# Sheet1.net
KiCad netlist of a schematic drawn in Altium Designer
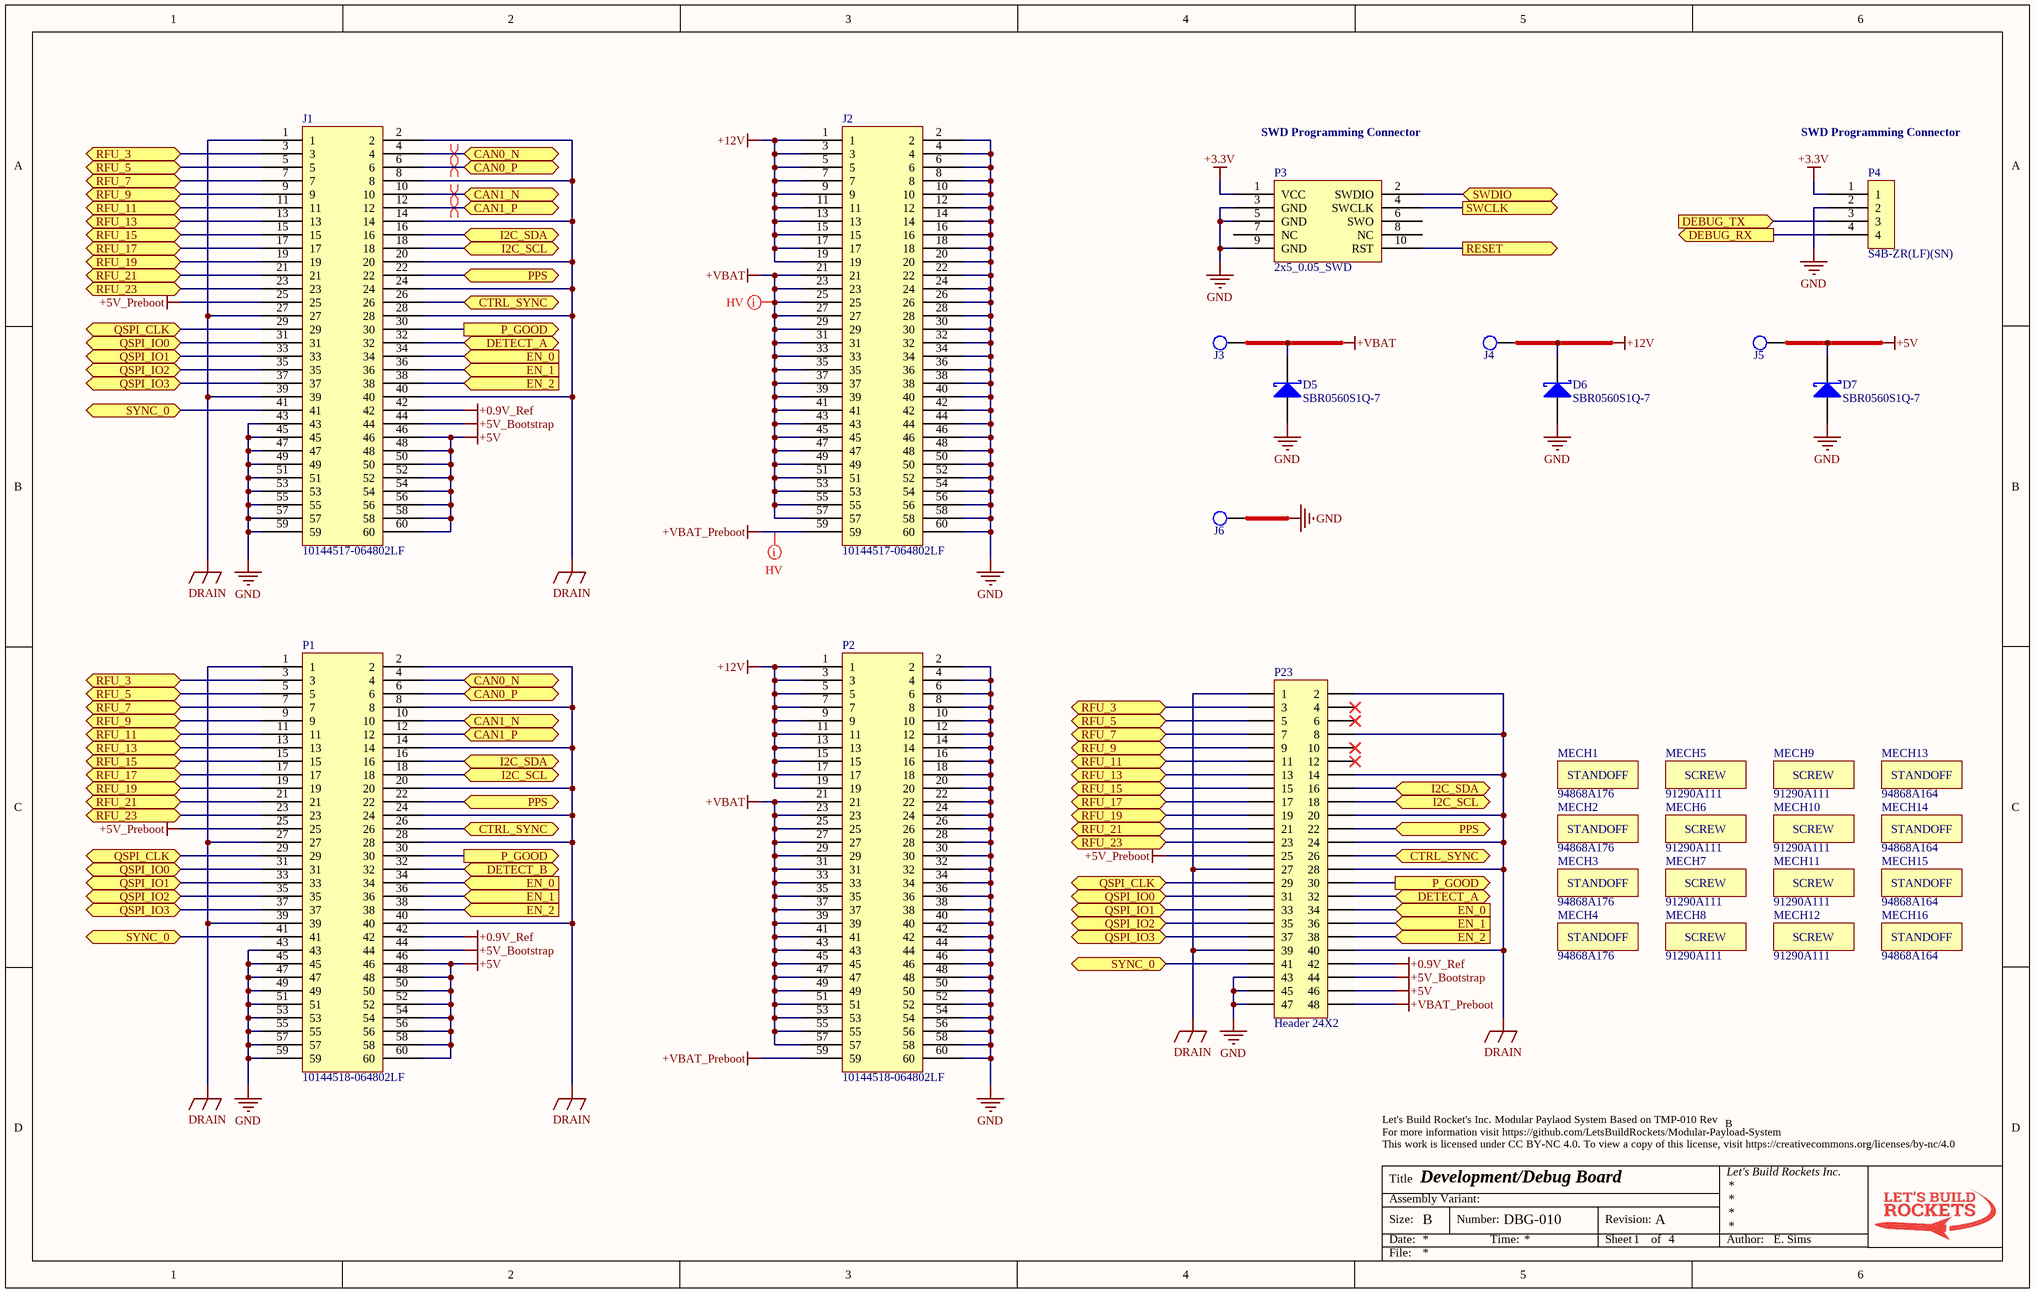
[diagram p0: Sheet1.SchDoc]

(export (version "E")
  (design (tool "Eeschema 10.0.6"))
  (components
    (comp (ref "D5")
      (value "SBR0560S1Q-7")
      (footprint "SOD123")
      (libsource (lib "ModularPayload") (part "SBR0560S1Q-7"))
    )
    (comp (ref "D6")
      (value "SBR0560S1Q-7")
      (footprint "SOD123")
      (libsource (lib "ModularPayload") (part "SBR0560S1Q-7"))
    )
    (comp (ref "D7")
      (value "SBR0560S1Q-7")
      (footprint "SOD123")
      (libsource (lib "ModularPayload") (part "SBR0560S1Q-7"))
    )
    (comp (ref "J1")
      (value "10144517-064802LF")
      (footprint "10144517-064802LF")
      (libsource (lib "ModularPayload") (part "10144517-064802LF"))
    )
    (comp (ref "J2")
      (value "10144517-064802LF")
      (footprint "10144517-064802LF")
      (libsource (lib "ModularPayload") (part "10144517-064802LF"))
    )
    (comp (ref "J3") (value "Banana") (footprint "CT3151SP-2") (libsource (lib "TP") (part "CT3151SP-2")))
    (comp (ref "J4") (value "Banana") (footprint "CT3151SP-2") (libsource (lib "TP") (part "CT3151SP-2")))
    (comp (ref "J5") (value "Banana") (footprint "CT3151SP-2") (libsource (lib "TP") (part "CT3151SP-2")))
    (comp (ref "J6") (value "Banana") (footprint "CT3151SP-0") (libsource (lib "TP") (part "CT3151SP-0")))
    (comp (ref "MECH1")
      (value "94868A176")
      (footprint "94868A176")
      (libsource (lib "ModularPayload") (part "94868A176"))
    )
    (comp (ref "MECH2")
      (value "94868A176")
      (footprint "94868A176")
      (libsource (lib "ModularPayload") (part "94868A176"))
    )
    (comp (ref "MECH3")
      (value "94868A176")
      (footprint "94868A176")
      (libsource (lib "ModularPayload") (part "94868A176"))
    )
    (comp (ref "MECH4")
      (value "94868A176")
      (footprint "94868A176")
      (libsource (lib "ModularPayload") (part "94868A176"))
    )
    (comp (ref "MECH5")
      (value "91290A111")
      (footprint "91290A111")
      (libsource (lib "ModularPayload") (part "91290A111"))
    )
    (comp (ref "MECH6")
      (value "91290A111")
      (footprint "91290A111")
      (libsource (lib "ModularPayload") (part "91290A111"))
    )
    (comp (ref "MECH7")
      (value "91290A111")
      (footprint "91290A111")
      (libsource (lib "ModularPayload") (part "91290A111"))
    )
    (comp (ref "MECH8")
      (value "91290A111")
      (footprint "91290A111")
      (libsource (lib "ModularPayload") (part "91290A111"))
    )
    (comp (ref "MECH9")
      (value "91290A111")
      (footprint "91290A111")
      (libsource (lib "ModularPayload") (part "91290A111"))
    )
    (comp (ref "MECH10")
      (value "91290A111")
      (footprint "91290A111")
      (libsource (lib "ModularPayload") (part "91290A111"))
    )
    (comp (ref "MECH11")
      (value "91290A111")
      (footprint "91290A111")
      (libsource (lib "ModularPayload") (part "91290A111"))
    )
    (comp (ref "MECH12")
      (value "91290A111")
      (footprint "91290A111")
      (libsource (lib "ModularPayload") (part "91290A111"))
    )
    (comp (ref "MECH13")
      (value "94868A164")
      (footprint "94868A164")
      (libsource (lib "ModularPayload") (part "94868A164"))
    )
    (comp (ref "MECH14")
      (value "94868A164")
      (footprint "94868A164")
      (libsource (lib "ModularPayload") (part "94868A164"))
    )
    (comp (ref "MECH15")
      (value "94868A164")
      (footprint "94868A164")
      (libsource (lib "ModularPayload") (part "94868A164"))
    )
    (comp (ref "MECH16")
      (value "94868A164")
      (footprint "94868A164")
      (libsource (lib "ModularPayload") (part "94868A164"))
    )
    (comp (ref "P1")
      (value "10144518-064802LF")
      (footprint "10144518-064802LF")
      (libsource (lib "ModularPayload") (part "10144518-064802LF"))
    )
    (comp (ref "P2")
      (value "10144518-064802LF")
      (footprint "10144518-064802LF")
      (libsource (lib "ModularPayload") (part "10144518-064802LF"))
    )
    (comp (ref "P3")
      (value "2x5_0.05_SWD")
      (footprint "2x5_0.05_R")
      (libsource (lib "ModularPayload") (part "2x5_0.05_SWD"))
    )
    (comp (ref "P4")
      (value "S4B-ZR(LF)(SN)")
      (footprint "S4B-ZR(LF)(SN)")
      (libsource (lib "ModularPayload") (part "S4B-ZR(LF)(SN)"))
    )
    (comp (ref "P23")
      (value "Header 24X2")
      (footprint "HDR2X24")
      (description "Header, 24-Pin, Dual row")
      (fields (field (name "PUBLISHER") "Altium Limited"))
      (libsource (lib "Miscellaneous Connectors") (part "Header 24X2"))
    )
  )
  (nets
    (net (code "1") (name "+0.9V_Ref") (class "Default")
      (node (ref "J1") (pin "42") (pinfunction "42_42") (pintype "passive"))
      (node (ref "P1") (pin "42") (pinfunction "42_42") (pintype "passive"))
      (node (ref "P23") (pin "42") (pinfunction "42_42") (pintype "passive"))
    )
    (net (code "2") (name "+3.3V") (class "Default")
      (node (ref "P3") (pin "1") (pinfunction "VCC_1") (pintype "passive"))
      (node (ref "P4") (pin "1") (pinfunction "1_1") (pintype "passive"))
    )
    (net (code "3") (name "+5V") (class "Default")
      (node (ref "D7") (pin "K") (pinfunction "K_K") (pintype "passive"))
      (node (ref "J1") (pin "46") (pinfunction "46_46") (pintype "passive"))
      (node (ref "J1") (pin "48") (pinfunction "48_48") (pintype "passive"))
      (node (ref "J1") (pin "50") (pinfunction "50_50") (pintype "passive"))
      (node (ref "J1") (pin "52") (pinfunction "52_52") (pintype "passive"))
      (node (ref "J1") (pin "54") (pinfunction "54_54") (pintype "passive"))
      (node (ref "J1") (pin "56") (pinfunction "56_56") (pintype "passive"))
      (node (ref "J1") (pin "58") (pinfunction "58_58") (pintype "passive"))
      (node (ref "J1") (pin "60") (pinfunction "60_60") (pintype "passive"))
      (node (ref "J5") (pin "1") (pintype "passive"))
      (node (ref "P1") (pin "46") (pinfunction "46_46") (pintype "passive"))
      (node (ref "P1") (pin "48") (pinfunction "48_48") (pintype "passive"))
      (node (ref "P1") (pin "50") (pinfunction "50_50") (pintype "passive"))
      (node (ref "P1") (pin "52") (pinfunction "52_52") (pintype "passive"))
      (node (ref "P1") (pin "54") (pinfunction "54_54") (pintype "passive"))
      (node (ref "P1") (pin "56") (pinfunction "56_56") (pintype "passive"))
      (node (ref "P1") (pin "58") (pinfunction "58_58") (pintype "passive"))
      (node (ref "P1") (pin "60") (pinfunction "60_60") (pintype "passive"))
      (node (ref "P23") (pin "46") (pinfunction "46_46") (pintype "passive"))
    )
    (net (code "4") (name "+5V_Bootstrap") (class "Default")
      (node (ref "J1") (pin "44") (pinfunction "44_44") (pintype "passive"))
      (node (ref "P1") (pin "44") (pinfunction "44_44") (pintype "passive"))
      (node (ref "P23") (pin "44") (pinfunction "44_44") (pintype "passive"))
    )
    (net (code "5") (name "+5V_Preboot") (class "Default")
      (node (ref "J1") (pin "25") (pinfunction "25_25") (pintype "passive"))
      (node (ref "P1") (pin "25") (pinfunction "25_25") (pintype "passive"))
      (node (ref "P23") (pin "25") (pinfunction "25_25") (pintype "passive"))
    )
    (net (code "6") (name "+12V") (class "Default")
      (node (ref "D6") (pin "K") (pinfunction "K_K") (pintype "passive"))
      (node (ref "J2") (pin "1") (pinfunction "1_1") (pintype "passive"))
      (node (ref "J2") (pin "11") (pinfunction "11_11") (pintype "passive"))
      (node (ref "J2") (pin "13") (pinfunction "13_13") (pintype "passive"))
      (node (ref "J2") (pin "15") (pinfunction "15_15") (pintype "passive"))
      (node (ref "J2") (pin "17") (pinfunction "17_17") (pintype "passive"))
      (node (ref "J2") (pin "19") (pinfunction "19_19") (pintype "passive"))
      (node (ref "J2") (pin "3") (pinfunction "3_3") (pintype "passive"))
      (node (ref "J2") (pin "5") (pinfunction "5_5") (pintype "passive"))
      (node (ref "J2") (pin "7") (pinfunction "7_7") (pintype "passive"))
      (node (ref "J2") (pin "9") (pinfunction "9_9") (pintype "passive"))
      (node (ref "J4") (pin "1") (pintype "passive"))
      (node (ref "P2") (pin "1") (pinfunction "1_1") (pintype "passive"))
      (node (ref "P2") (pin "11") (pinfunction "11_11") (pintype "passive"))
      (node (ref "P2") (pin "13") (pinfunction "13_13") (pintype "passive"))
      (node (ref "P2") (pin "15") (pinfunction "15_15") (pintype "passive"))
      (node (ref "P2") (pin "17") (pinfunction "17_17") (pintype "passive"))
      (node (ref "P2") (pin "19") (pinfunction "19_19") (pintype "passive"))
      (node (ref "P2") (pin "3") (pinfunction "3_3") (pintype "passive"))
      (node (ref "P2") (pin "5") (pinfunction "5_5") (pintype "passive"))
      (node (ref "P2") (pin "7") (pinfunction "7_7") (pintype "passive"))
      (node (ref "P2") (pin "9") (pinfunction "9_9") (pintype "passive"))
    )
    (net (code "7") (name "+VBAT") (class "Default")
      (node (ref "D5") (pin "K") (pinfunction "K_K") (pintype "passive"))
      (node (ref "J2") (pin "21") (pinfunction "21_21") (pintype "passive"))
      (node (ref "J2") (pin "23") (pinfunction "23_23") (pintype "passive"))
      (node (ref "J2") (pin "25") (pinfunction "25_25") (pintype "passive"))
      (node (ref "J2") (pin "27") (pinfunction "27_27") (pintype "passive"))
      (node (ref "J2") (pin "29") (pinfunction "29_29") (pintype "passive"))
      (node (ref "J2") (pin "31") (pinfunction "31_31") (pintype "passive"))
      (node (ref "J2") (pin "33") (pinfunction "33_33") (pintype "passive"))
      (node (ref "J2") (pin "35") (pinfunction "35_35") (pintype "passive"))
      (node (ref "J2") (pin "37") (pinfunction "37_37") (pintype "passive"))
      (node (ref "J2") (pin "39") (pinfunction "39_39") (pintype "passive"))
      (node (ref "J2") (pin "41") (pinfunction "41_41") (pintype "passive"))
      (node (ref "J2") (pin "43") (pinfunction "43_43") (pintype "passive"))
      (node (ref "J2") (pin "45") (pinfunction "45_45") (pintype "passive"))
      (node (ref "J2") (pin "47") (pinfunction "47_47") (pintype "passive"))
      (node (ref "J2") (pin "49") (pinfunction "49_49") (pintype "passive"))
      (node (ref "J2") (pin "51") (pinfunction "51_51") (pintype "passive"))
      (node (ref "J2") (pin "53") (pinfunction "53_53") (pintype "passive"))
      (node (ref "J2") (pin "55") (pinfunction "55_55") (pintype "passive"))
      (node (ref "J2") (pin "57") (pinfunction "57_57") (pintype "passive"))
      (node (ref "J3") (pin "1") (pintype "passive"))
      (node (ref "P2") (pin "21") (pinfunction "21_21") (pintype "passive"))
      (node (ref "P2") (pin "23") (pinfunction "23_23") (pintype "passive"))
      (node (ref "P2") (pin "25") (pinfunction "25_25") (pintype "passive"))
      (node (ref "P2") (pin "27") (pinfunction "27_27") (pintype "passive"))
      (node (ref "P2") (pin "29") (pinfunction "29_29") (pintype "passive"))
      (node (ref "P2") (pin "31") (pinfunction "31_31") (pintype "passive"))
      (node (ref "P2") (pin "33") (pinfunction "33_33") (pintype "passive"))
      (node (ref "P2") (pin "35") (pinfunction "35_35") (pintype "passive"))
      (node (ref "P2") (pin "37") (pinfunction "37_37") (pintype "passive"))
      (node (ref "P2") (pin "39") (pinfunction "39_39") (pintype "passive"))
      (node (ref "P2") (pin "41") (pinfunction "41_41") (pintype "passive"))
      (node (ref "P2") (pin "43") (pinfunction "43_43") (pintype "passive"))
      (node (ref "P2") (pin "45") (pinfunction "45_45") (pintype "passive"))
      (node (ref "P2") (pin "47") (pinfunction "47_47") (pintype "passive"))
      (node (ref "P2") (pin "49") (pinfunction "49_49") (pintype "passive"))
      (node (ref "P2") (pin "51") (pinfunction "51_51") (pintype "passive"))
      (node (ref "P2") (pin "53") (pinfunction "53_53") (pintype "passive"))
      (node (ref "P2") (pin "55") (pinfunction "55_55") (pintype "passive"))
      (node (ref "P2") (pin "57") (pinfunction "57_57") (pintype "passive"))
    )
    (net (code "8") (name "+VBAT_Preboot") (class "Default")
      (node (ref "J2") (pin "59") (pinfunction "59_59") (pintype "passive"))
      (node (ref "P2") (pin "59") (pinfunction "59_59") (pintype "passive"))
      (node (ref "P23") (pin "48") (pinfunction "48_48") (pintype "passive"))
    )
    (net (code "9") (name "/CAN0_N") (class "Default")
      (node (ref "J1") (pin "4") (pinfunction "4_4") (pintype "passive"))
      (node (ref "P1") (pin "4") (pinfunction "4_4") (pintype "passive"))
    )
    (net (code "10") (name "/CAN0_P") (class "Default")
      (node (ref "J1") (pin "6") (pinfunction "6_6") (pintype "passive"))
      (node (ref "P1") (pin "6") (pinfunction "6_6") (pintype "passive"))
    )
    (net (code "11") (name "/CAN1_N") (class "Default")
      (node (ref "J1") (pin "10") (pinfunction "10_10") (pintype "passive"))
      (node (ref "P1") (pin "10") (pinfunction "10_10") (pintype "passive"))
    )
    (net (code "12") (name "/CAN1_P") (class "Default")
      (node (ref "J1") (pin "12") (pinfunction "12_12") (pintype "passive"))
      (node (ref "P1") (pin "12") (pinfunction "12_12") (pintype "passive"))
    )
    (net (code "13") (name "/CTRL_SYNC") (class "Default")
      (node (ref "J1") (pin "26") (pinfunction "26_26") (pintype "passive"))
      (node (ref "P1") (pin "26") (pinfunction "26_26") (pintype "passive"))
      (node (ref "P23") (pin "26") (pinfunction "26_26") (pintype "passive"))
    )
    (net (code "14") (name "/DEBUG_RX") (class "Default")
      (node (ref "P4") (pin "4") (pinfunction "4_4") (pintype "passive"))
    )
    (net (code "15") (name "/DEBUG_TX") (class "Default")
      (node (ref "P4") (pin "3") (pinfunction "3_3") (pintype "passive"))
    )
    (net (code "16") (name "/DETECT_A") (class "Default")
      (node (ref "J1") (pin "32") (pinfunction "32_32") (pintype "passive"))
      (node (ref "P23") (pin "32") (pinfunction "32_32") (pintype "passive"))
    )
    (net (code "17") (name "/DETECT_B") (class "Default")
      (node (ref "P1") (pin "32") (pinfunction "32_32") (pintype "passive"))
    )
    (net (code "18") (name "/EN_0") (class "Default")
      (node (ref "J1") (pin "34") (pinfunction "34_34") (pintype "passive"))
      (node (ref "P1") (pin "34") (pinfunction "34_34") (pintype "passive"))
      (node (ref "P23") (pin "34") (pinfunction "34_34") (pintype "passive"))
    )
    (net (code "19") (name "/EN_1") (class "Default")
      (node (ref "J1") (pin "36") (pinfunction "36_36") (pintype "passive"))
      (node (ref "P1") (pin "36") (pinfunction "36_36") (pintype "passive"))
      (node (ref "P23") (pin "36") (pinfunction "36_36") (pintype "passive"))
    )
    (net (code "20") (name "/EN_2") (class "Default")
      (node (ref "J1") (pin "38") (pinfunction "38_38") (pintype "passive"))
      (node (ref "P1") (pin "38") (pinfunction "38_38") (pintype "passive"))
      (node (ref "P23") (pin "38") (pinfunction "38_38") (pintype "passive"))
    )
    (net (code "21") (name "/I2C_SCL") (class "Default")
      (node (ref "J1") (pin "18") (pinfunction "18_18") (pintype "passive"))
      (node (ref "P1") (pin "18") (pinfunction "18_18") (pintype "passive"))
      (node (ref "P23") (pin "18") (pinfunction "18_18") (pintype "passive"))
    )
    (net (code "22") (name "/I2C_SDA") (class "Default")
      (node (ref "J1") (pin "16") (pinfunction "16_16") (pintype "passive"))
      (node (ref "P1") (pin "16") (pinfunction "16_16") (pintype "passive"))
      (node (ref "P23") (pin "16") (pinfunction "16_16") (pintype "passive"))
    )
    (net (code "23") (name "/PPS") (class "Default")
      (node (ref "J1") (pin "22") (pinfunction "22_22") (pintype "passive"))
      (node (ref "P1") (pin "22") (pinfunction "22_22") (pintype "passive"))
      (node (ref "P23") (pin "22") (pinfunction "22_22") (pintype "passive"))
    )
    (net (code "24") (name "/P_GOOD") (class "Default")
      (node (ref "J1") (pin "30") (pinfunction "30_30") (pintype "passive"))
      (node (ref "P1") (pin "30") (pinfunction "30_30") (pintype "passive"))
      (node (ref "P23") (pin "30") (pinfunction "30_30") (pintype "passive"))
    )
    (net (code "25") (name "/QSPI_CLK") (class "Default")
      (node (ref "J1") (pin "29") (pinfunction "29_29") (pintype "passive"))
      (node (ref "P1") (pin "29") (pinfunction "29_29") (pintype "passive"))
      (node (ref "P23") (pin "29") (pinfunction "29_29") (pintype "passive"))
    )
    (net (code "26") (name "/QSPI_IO0") (class "Default")
      (node (ref "J1") (pin "31") (pinfunction "31_31") (pintype "passive"))
      (node (ref "P1") (pin "31") (pinfunction "31_31") (pintype "passive"))
      (node (ref "P23") (pin "31") (pinfunction "31_31") (pintype "passive"))
    )
    (net (code "27") (name "/QSPI_IO1") (class "Default")
      (node (ref "J1") (pin "33") (pinfunction "33_33") (pintype "passive"))
      (node (ref "P1") (pin "33") (pinfunction "33_33") (pintype "passive"))
      (node (ref "P23") (pin "33") (pinfunction "33_33") (pintype "passive"))
    )
    (net (code "28") (name "/QSPI_IO2") (class "Default")
      (node (ref "J1") (pin "35") (pinfunction "35_35") (pintype "passive"))
      (node (ref "P1") (pin "35") (pinfunction "35_35") (pintype "passive"))
      (node (ref "P23") (pin "35") (pinfunction "35_35") (pintype "passive"))
    )
    (net (code "29") (name "/QSPI_IO3") (class "Default")
      (node (ref "J1") (pin "37") (pinfunction "37_37") (pintype "passive"))
      (node (ref "P1") (pin "37") (pinfunction "37_37") (pintype "passive"))
      (node (ref "P23") (pin "37") (pinfunction "37_37") (pintype "passive"))
    )
    (net (code "30") (name "/RESET") (class "Default")
      (node (ref "P3") (pin "10") (pinfunction "RST_10") (pintype "passive"))
    )
    (net (code "31") (name "/RFU_3") (class "Default")
      (node (ref "J1") (pin "3") (pinfunction "3_3") (pintype "passive"))
      (node (ref "P1") (pin "3") (pinfunction "3_3") (pintype "passive"))
      (node (ref "P23") (pin "3") (pinfunction "3_3") (pintype "passive"))
    )
    (net (code "32") (name "/RFU_5") (class "Default")
      (node (ref "J1") (pin "5") (pinfunction "5_5") (pintype "passive"))
      (node (ref "P1") (pin "5") (pinfunction "5_5") (pintype "passive"))
      (node (ref "P23") (pin "5") (pinfunction "5_5") (pintype "passive"))
    )
    (net (code "33") (name "/RFU_7") (class "Default")
      (node (ref "J1") (pin "7") (pinfunction "7_7") (pintype "passive"))
      (node (ref "P1") (pin "7") (pinfunction "7_7") (pintype "passive"))
      (node (ref "P23") (pin "7") (pinfunction "7_7") (pintype "passive"))
    )
    (net (code "34") (name "/RFU_9") (class "Default")
      (node (ref "J1") (pin "9") (pinfunction "9_9") (pintype "passive"))
      (node (ref "P1") (pin "9") (pinfunction "9_9") (pintype "passive"))
      (node (ref "P23") (pin "9") (pinfunction "9_9") (pintype "passive"))
    )
    (net (code "35") (name "/RFU_11") (class "Default")
      (node (ref "J1") (pin "11") (pinfunction "11_11") (pintype "passive"))
      (node (ref "P1") (pin "11") (pinfunction "11_11") (pintype "passive"))
      (node (ref "P23") (pin "11") (pinfunction "11_11") (pintype "passive"))
    )
    (net (code "36") (name "/RFU_13") (class "Default")
      (node (ref "J1") (pin "13") (pinfunction "13_13") (pintype "passive"))
      (node (ref "P1") (pin "13") (pinfunction "13_13") (pintype "passive"))
      (node (ref "P23") (pin "13") (pinfunction "13_13") (pintype "passive"))
    )
    (net (code "37") (name "/RFU_15") (class "Default")
      (node (ref "J1") (pin "15") (pinfunction "15_15") (pintype "passive"))
      (node (ref "P1") (pin "15") (pinfunction "15_15") (pintype "passive"))
      (node (ref "P23") (pin "15") (pinfunction "15_15") (pintype "passive"))
    )
    (net (code "38") (name "/RFU_17") (class "Default")
      (node (ref "J1") (pin "17") (pinfunction "17_17") (pintype "passive"))
      (node (ref "P1") (pin "17") (pinfunction "17_17") (pintype "passive"))
      (node (ref "P23") (pin "17") (pinfunction "17_17") (pintype "passive"))
    )
    (net (code "39") (name "/RFU_19") (class "Default")
      (node (ref "J1") (pin "19") (pinfunction "19_19") (pintype "passive"))
      (node (ref "P1") (pin "19") (pinfunction "19_19") (pintype "passive"))
      (node (ref "P23") (pin "19") (pinfunction "19_19") (pintype "passive"))
    )
    (net (code "40") (name "/RFU_21") (class "Default")
      (node (ref "J1") (pin "21") (pinfunction "21_21") (pintype "passive"))
      (node (ref "P1") (pin "21") (pinfunction "21_21") (pintype "passive"))
      (node (ref "P23") (pin "21") (pinfunction "21_21") (pintype "passive"))
    )
    (net (code "41") (name "/RFU_23") (class "Default")
      (node (ref "J1") (pin "23") (pinfunction "23_23") (pintype "passive"))
      (node (ref "P1") (pin "23") (pinfunction "23_23") (pintype "passive"))
      (node (ref "P23") (pin "23") (pinfunction "23_23") (pintype "passive"))
    )
    (net (code "42") (name "/SWCLK") (class "Default")
      (node (ref "P3") (pin "4") (pinfunction "SWCLK_4") (pintype "passive"))
    )
    (net (code "43") (name "/SWDIO") (class "Default")
      (node (ref "P3") (pin "2") (pinfunction "SWDIO_2") (pintype "passive"))
    )
    (net (code "44") (name "/SYNC_0") (class "Default")
      (node (ref "J1") (pin "41") (pinfunction "41_41") (pintype "passive"))
      (node (ref "P1") (pin "41") (pinfunction "41_41") (pintype "passive"))
      (node (ref "P23") (pin "41") (pinfunction "41_41") (pintype "passive"))
    )
    (net (code "45") (name "DRAIN") (class "Default")
      (node (ref "J1") (pin "1") (pinfunction "1_1") (pintype "passive"))
      (node (ref "J1") (pin "14") (pinfunction "14_14") (pintype "passive"))
      (node (ref "J1") (pin "2") (pinfunction "2_2") (pintype "passive"))
      (node (ref "J1") (pin "20") (pinfunction "20_20") (pintype "passive"))
      (node (ref "J1") (pin "24") (pinfunction "24_24") (pintype "passive"))
      (node (ref "J1") (pin "27") (pinfunction "27_27") (pintype "passive"))
      (node (ref "J1") (pin "28") (pinfunction "28_28") (pintype "passive"))
      (node (ref "J1") (pin "39") (pinfunction "39_39") (pintype "passive"))
      (node (ref "J1") (pin "40") (pinfunction "40_40") (pintype "passive"))
      (node (ref "J1") (pin "8") (pinfunction "8_8") (pintype "passive"))
      (node (ref "P1") (pin "1") (pinfunction "1_1") (pintype "passive"))
      (node (ref "P1") (pin "14") (pinfunction "14_14") (pintype "passive"))
      (node (ref "P1") (pin "2") (pinfunction "2_2") (pintype "passive"))
      (node (ref "P1") (pin "20") (pinfunction "20_20") (pintype "passive"))
      (node (ref "P1") (pin "24") (pinfunction "24_24") (pintype "passive"))
      (node (ref "P1") (pin "27") (pinfunction "27_27") (pintype "passive"))
      (node (ref "P1") (pin "28") (pinfunction "28_28") (pintype "passive"))
      (node (ref "P1") (pin "39") (pinfunction "39_39") (pintype "passive"))
      (node (ref "P1") (pin "40") (pinfunction "40_40") (pintype "passive"))
      (node (ref "P1") (pin "8") (pinfunction "8_8") (pintype "passive"))
      (node (ref "P23") (pin "1") (pinfunction "1_1") (pintype "passive"))
      (node (ref "P23") (pin "14") (pinfunction "14_14") (pintype "passive"))
      (node (ref "P23") (pin "2") (pinfunction "2_2") (pintype "passive"))
      (node (ref "P23") (pin "20") (pinfunction "20_20") (pintype "passive"))
      (node (ref "P23") (pin "24") (pinfunction "24_24") (pintype "passive"))
      (node (ref "P23") (pin "27") (pinfunction "27_27") (pintype "passive"))
      (node (ref "P23") (pin "28") (pinfunction "28_28") (pintype "passive"))
      (node (ref "P23") (pin "39") (pinfunction "39_39") (pintype "passive"))
      (node (ref "P23") (pin "40") (pinfunction "40_40") (pintype "passive"))
      (node (ref "P23") (pin "8") (pinfunction "8_8") (pintype "passive"))
    )
    (net (code "46") (name "GND") (class "Default")
      (node (ref "D5") (pin "A") (pinfunction "A_A") (pintype "passive"))
      (node (ref "D6") (pin "A") (pinfunction "A_A") (pintype "passive"))
      (node (ref "D7") (pin "A") (pinfunction "A_A") (pintype "passive"))
      (node (ref "J1") (pin "43") (pinfunction "43_43") (pintype "passive"))
      (node (ref "J1") (pin "45") (pinfunction "45_45") (pintype "passive"))
      (node (ref "J1") (pin "47") (pinfunction "47_47") (pintype "passive"))
      (node (ref "J1") (pin "49") (pinfunction "49_49") (pintype "passive"))
      (node (ref "J1") (pin "51") (pinfunction "51_51") (pintype "passive"))
      (node (ref "J1") (pin "53") (pinfunction "53_53") (pintype "passive"))
      (node (ref "J1") (pin "55") (pinfunction "55_55") (pintype "passive"))
      (node (ref "J1") (pin "57") (pinfunction "57_57") (pintype "passive"))
      (node (ref "J1") (pin "59") (pinfunction "59_59") (pintype "passive"))
      (node (ref "J2") (pin "10") (pinfunction "10_10") (pintype "passive"))
      (node (ref "J2") (pin "12") (pinfunction "12_12") (pintype "passive"))
      (node (ref "J2") (pin "14") (pinfunction "14_14") (pintype "passive"))
      (node (ref "J2") (pin "16") (pinfunction "16_16") (pintype "passive"))
      (node (ref "J2") (pin "18") (pinfunction "18_18") (pintype "passive"))
      (node (ref "J2") (pin "2") (pinfunction "2_2") (pintype "passive"))
      (node (ref "J2") (pin "20") (pinfunction "20_20") (pintype "passive"))
      (node (ref "J2") (pin "22") (pinfunction "22_22") (pintype "passive"))
      (node (ref "J2") (pin "24") (pinfunction "24_24") (pintype "passive"))
      (node (ref "J2") (pin "26") (pinfunction "26_26") (pintype "passive"))
      (node (ref "J2") (pin "28") (pinfunction "28_28") (pintype "passive"))
      (node (ref "J2") (pin "30") (pinfunction "30_30") (pintype "passive"))
      (node (ref "J2") (pin "32") (pinfunction "32_32") (pintype "passive"))
      (node (ref "J2") (pin "34") (pinfunction "34_34") (pintype "passive"))
      (node (ref "J2") (pin "36") (pinfunction "36_36") (pintype "passive"))
      (node (ref "J2") (pin "38") (pinfunction "38_38") (pintype "passive"))
      (node (ref "J2") (pin "4") (pinfunction "4_4") (pintype "passive"))
      (node (ref "J2") (pin "40") (pinfunction "40_40") (pintype "passive"))
      (node (ref "J2") (pin "42") (pinfunction "42_42") (pintype "passive"))
      (node (ref "J2") (pin "44") (pinfunction "44_44") (pintype "passive"))
      (node (ref "J2") (pin "46") (pinfunction "46_46") (pintype "passive"))
      (node (ref "J2") (pin "48") (pinfunction "48_48") (pintype "passive"))
      (node (ref "J2") (pin "50") (pinfunction "50_50") (pintype "passive"))
      (node (ref "J2") (pin "52") (pinfunction "52_52") (pintype "passive"))
      (node (ref "J2") (pin "54") (pinfunction "54_54") (pintype "passive"))
      (node (ref "J2") (pin "56") (pinfunction "56_56") (pintype "passive"))
      (node (ref "J2") (pin "58") (pinfunction "58_58") (pintype "passive"))
      (node (ref "J2") (pin "6") (pinfunction "6_6") (pintype "passive"))
      (node (ref "J2") (pin "60") (pinfunction "60_60") (pintype "passive"))
      (node (ref "J2") (pin "8") (pinfunction "8_8") (pintype "passive"))
      (node (ref "J6") (pin "1") (pintype "passive"))
      (node (ref "P1") (pin "43") (pinfunction "43_43") (pintype "passive"))
      (node (ref "P1") (pin "45") (pinfunction "45_45") (pintype "passive"))
      (node (ref "P1") (pin "47") (pinfunction "47_47") (pintype "passive"))
      (node (ref "P1") (pin "49") (pinfunction "49_49") (pintype "passive"))
      (node (ref "P1") (pin "51") (pinfunction "51_51") (pintype "passive"))
      (node (ref "P1") (pin "53") (pinfunction "53_53") (pintype "passive"))
      (node (ref "P1") (pin "55") (pinfunction "55_55") (pintype "passive"))
      (node (ref "P1") (pin "57") (pinfunction "57_57") (pintype "passive"))
      (node (ref "P1") (pin "59") (pinfunction "59_59") (pintype "passive"))
      (node (ref "P2") (pin "10") (pinfunction "10_10") (pintype "passive"))
      (node (ref "P2") (pin "12") (pinfunction "12_12") (pintype "passive"))
      (node (ref "P2") (pin "14") (pinfunction "14_14") (pintype "passive"))
      (node (ref "P2") (pin "16") (pinfunction "16_16") (pintype "passive"))
      (node (ref "P2") (pin "18") (pinfunction "18_18") (pintype "passive"))
      (node (ref "P2") (pin "2") (pinfunction "2_2") (pintype "passive"))
      (node (ref "P2") (pin "20") (pinfunction "20_20") (pintype "passive"))
      (node (ref "P2") (pin "22") (pinfunction "22_22") (pintype "passive"))
      (node (ref "P2") (pin "24") (pinfunction "24_24") (pintype "passive"))
      (node (ref "P2") (pin "26") (pinfunction "26_26") (pintype "passive"))
      (node (ref "P2") (pin "28") (pinfunction "28_28") (pintype "passive"))
      (node (ref "P2") (pin "30") (pinfunction "30_30") (pintype "passive"))
      (node (ref "P2") (pin "32") (pinfunction "32_32") (pintype "passive"))
      (node (ref "P2") (pin "34") (pinfunction "34_34") (pintype "passive"))
      (node (ref "P2") (pin "36") (pinfunction "36_36") (pintype "passive"))
      (node (ref "P2") (pin "38") (pinfunction "38_38") (pintype "passive"))
      (node (ref "P2") (pin "4") (pinfunction "4_4") (pintype "passive"))
      (node (ref "P2") (pin "40") (pinfunction "40_40") (pintype "passive"))
      (node (ref "P2") (pin "42") (pinfunction "42_42") (pintype "passive"))
      (node (ref "P2") (pin "44") (pinfunction "44_44") (pintype "passive"))
      (node (ref "P2") (pin "46") (pinfunction "46_46") (pintype "passive"))
      (node (ref "P2") (pin "48") (pinfunction "48_48") (pintype "passive"))
      (node (ref "P2") (pin "50") (pinfunction "50_50") (pintype "passive"))
      (node (ref "P2") (pin "52") (pinfunction "52_52") (pintype "passive"))
      (node (ref "P2") (pin "54") (pinfunction "54_54") (pintype "passive"))
      (node (ref "P2") (pin "56") (pinfunction "56_56") (pintype "passive"))
      (node (ref "P2") (pin "58") (pinfunction "58_58") (pintype "passive"))
      (node (ref "P2") (pin "6") (pinfunction "6_6") (pintype "passive"))
      (node (ref "P2") (pin "60") (pinfunction "60_60") (pintype "passive"))
      (node (ref "P2") (pin "8") (pinfunction "8_8") (pintype "passive"))
      (node (ref "P23") (pin "43") (pinfunction "43_43") (pintype "passive"))
      (node (ref "P23") (pin "45") (pinfunction "45_45") (pintype "passive"))
      (node (ref "P23") (pin "47") (pinfunction "47_47") (pintype "passive"))
      (node (ref "P3") (pin "3") (pinfunction "GND_3") (pintype "passive"))
      (node (ref "P3") (pin "5") (pinfunction "GND_5") (pintype "passive"))
      (node (ref "P3") (pin "9") (pinfunction "GND_9") (pintype "passive"))
      (node (ref "P4") (pin "2") (pinfunction "2_2") (pintype "passive"))
    )
    (net (code "47") (name "unconnected-(P3-NC-Pad7)") (class "Default")
      (node (ref "P3") (pin "7") (pinfunction "NC_7") (pintype "passive"))
    )
    (net (code "48") (name "unconnected-(P3-NC-Pad8)") (class "Default")
      (node (ref "P3") (pin "8") (pinfunction "NC_8") (pintype "passive"))
    )
    (net (code "49") (name "unconnected-(P3-SWO-Pad6)") (class "Default")
      (node (ref "P3") (pin "6") (pinfunction "SWO_6") (pintype "passive"))
    )
    (net (code "50") (name "unconnected-(P23-Pad4)") (class "Default")
      (node (ref "P23") (pin "4") (pinfunction "4_4") (pintype "passive+no_connect"))
    )
    (net (code "51") (name "unconnected-(P23-Pad6)") (class "Default")
      (node (ref "P23") (pin "6") (pinfunction "6_6") (pintype "passive+no_connect"))
    )
    (net (code "52") (name "unconnected-(P23-Pad10)") (class "Default")
      (node (ref "P23") (pin "10") (pinfunction "10_10") (pintype "passive+no_connect"))
    )
    (net (code "53") (name "unconnected-(P23-Pad12)") (class "Default")
      (node (ref "P23") (pin "12") (pinfunction "12_12") (pintype "passive+no_connect"))
    )
  )
)
